# P_04__CPU_POWER.net
KiCad netlist of a schematic drawn in Altium Designer
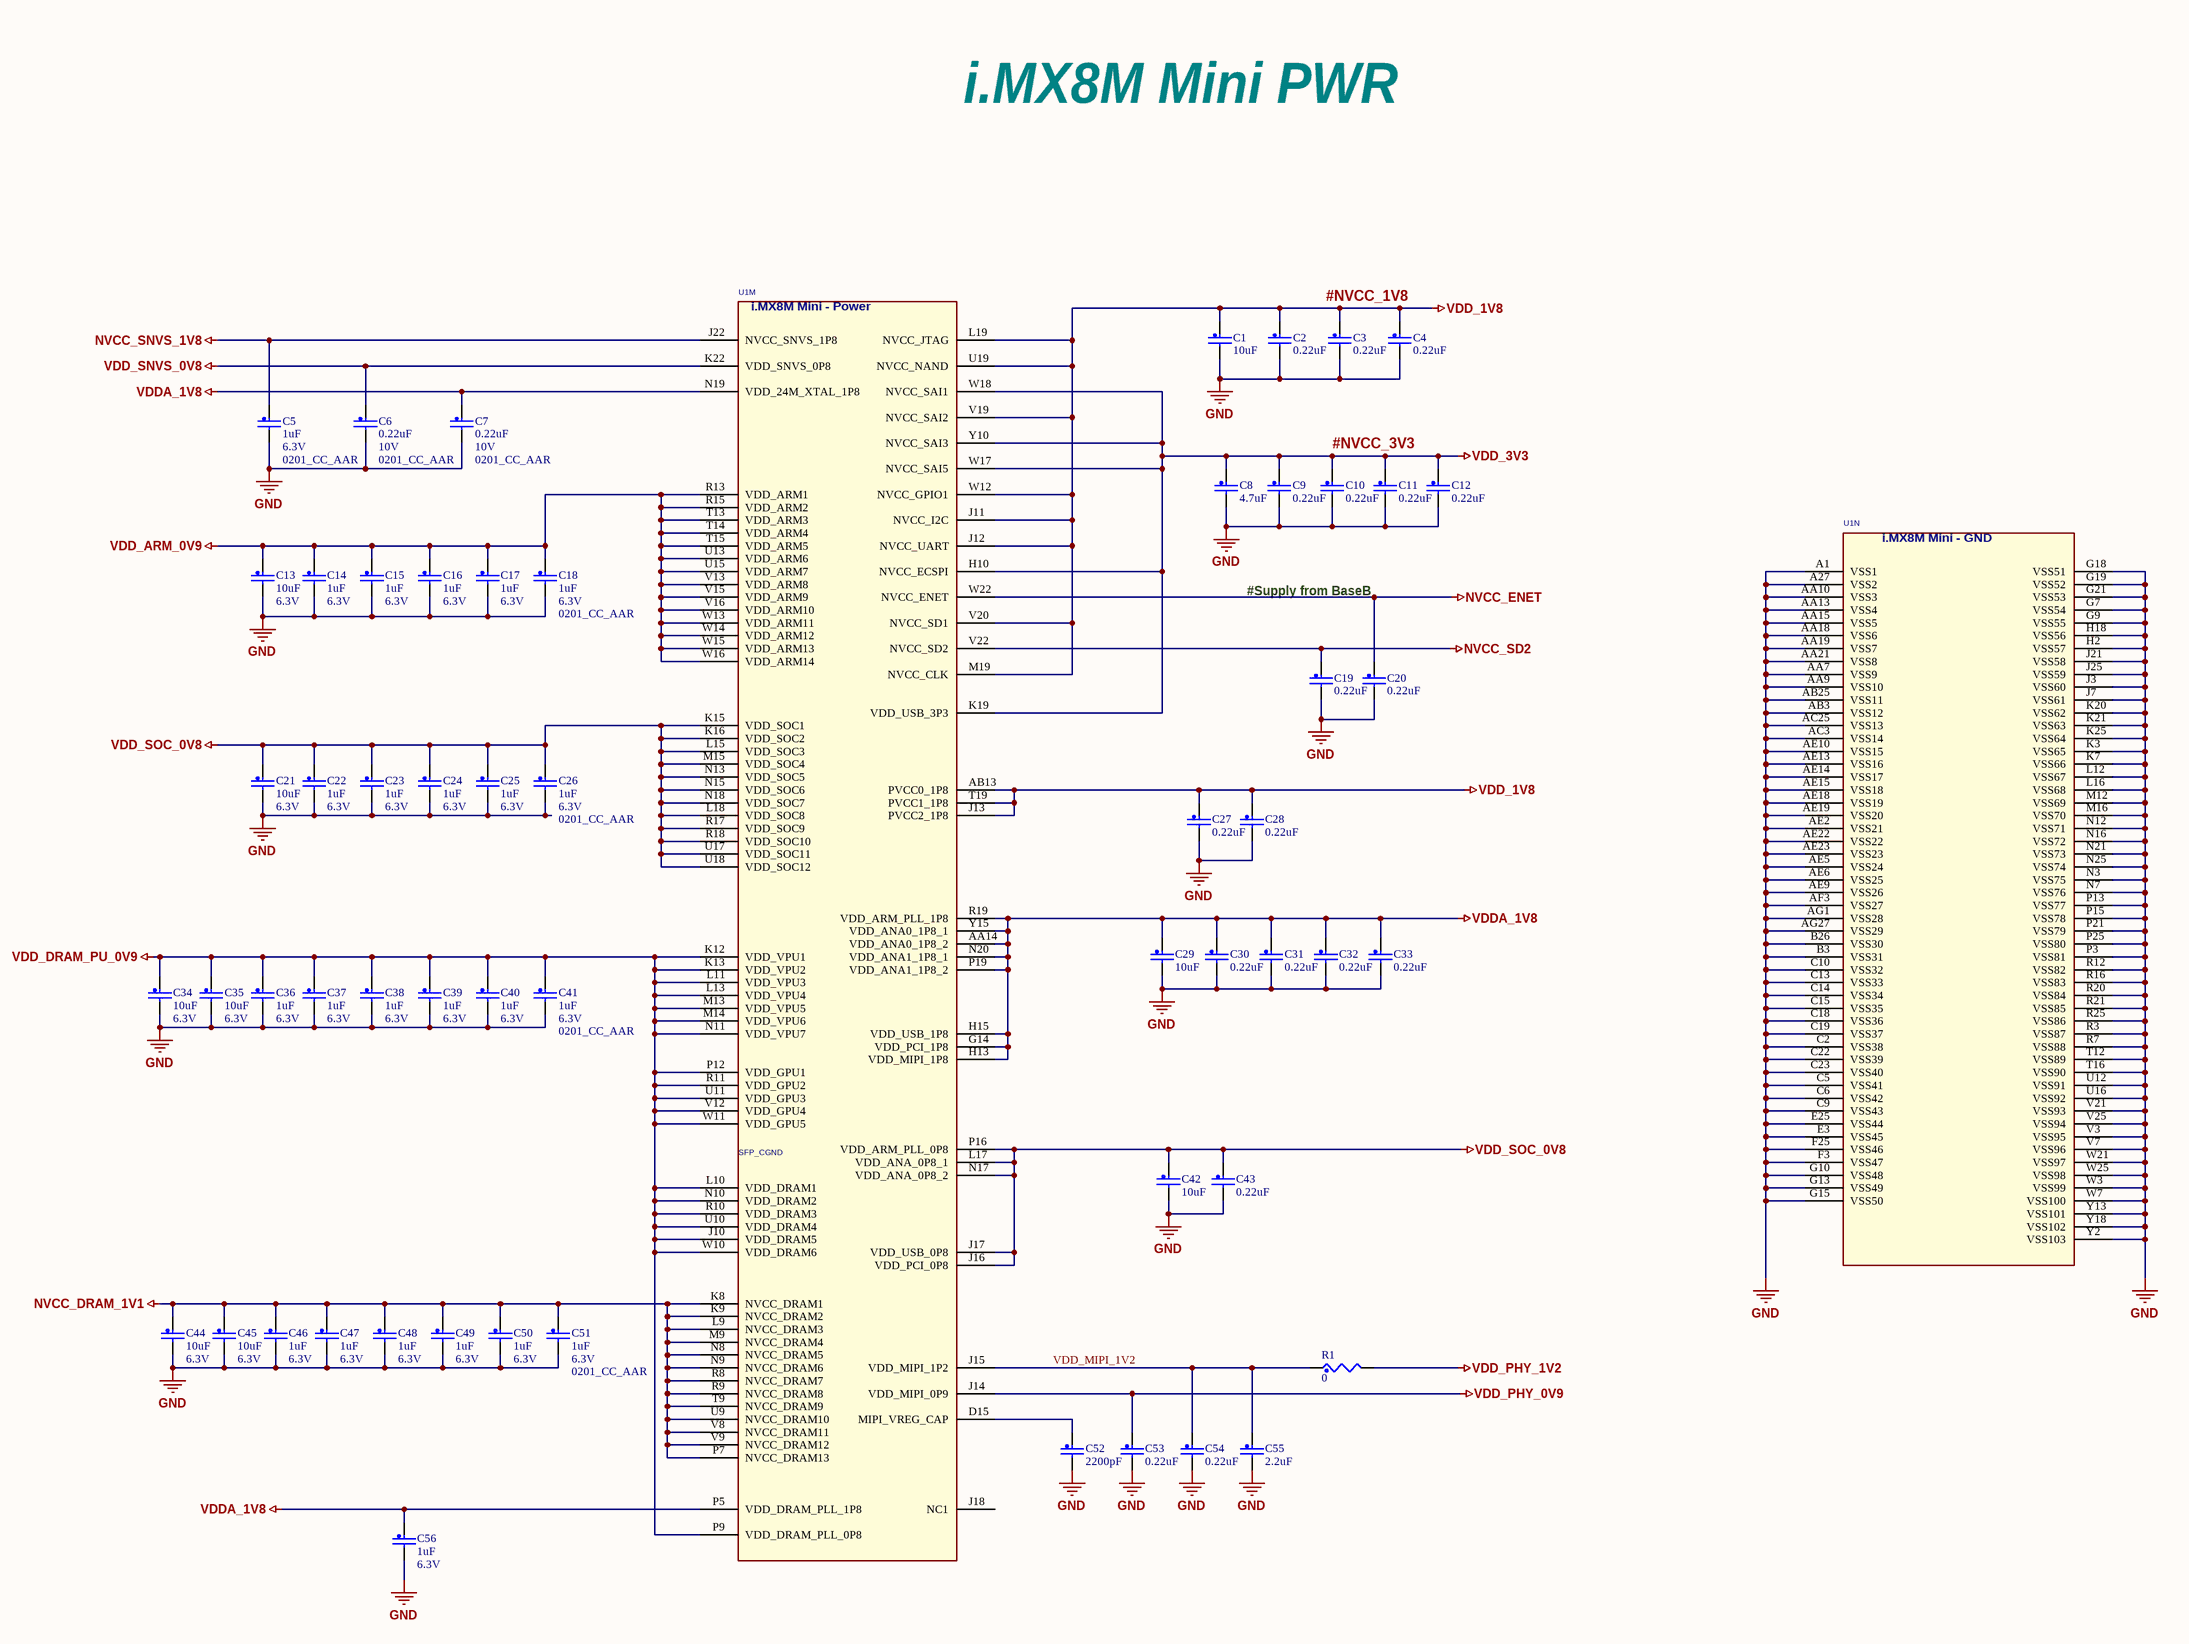
[diagram p0: P[04]_CPU_POWER.SchDoc]

(export (version "E")
  (design (tool "Eeschema 10.0.6"))
  (components
    (comp (ref "C1") (value "10uF") (footprint "0402_CC - C") (libsource (lib "AA_iMX8_M_") (part "CAP_NP")))
    (comp (ref "C2")
      (value "0.22uF")
      (footprint "0201_CC - C")
      (libsource (lib "AA_iMX8_M_") (part "CAP_NP"))
    )
    (comp (ref "C3")
      (value "0.22uF")
      (footprint "0201_CC - C")
      (libsource (lib "AA_iMX8_M_") (part "CAP_NP"))
    )
    (comp (ref "C4")
      (value "0.22uF")
      (footprint "0201_CC - C")
      (libsource (lib "AA_iMX8_M_") (part "CAP_NP"))
    )
    (comp (ref "C5")
      (value "1uF")
      (footprint "0201_CC_AAR")
      (fields (field (name "VOLTAGE") "6.3V"))
      (libsource (lib "AA_iMX8_M_") (part "CAP_NP"))
    )
    (comp (ref "C6")
      (value "0.22uF")
      (footprint "0201_CC_AAR")
      (fields (field (name "VOLTAGE") "10V"))
      (libsource (lib "AA_iMX8_M_") (part "CAP_NP"))
    )
    (comp (ref "C7")
      (value "0.22uF")
      (footprint "0201_CC_AAR")
      (fields (field (name "VOLTAGE") "10V"))
      (libsource (lib "AA_iMX8_M_") (part "CAP_NP"))
    )
    (comp (ref "C8") (value "4.7uF") (footprint "0402_CC - C") (libsource (lib "AA_iMX8_M_") (part "CAP_NP")))
    (comp (ref "C9")
      (value "0.22uF")
      (footprint "0201_CC - C")
      (libsource (lib "AA_iMX8_M_") (part "CAP_NP"))
    )
    (comp (ref "C10")
      (value "0.22uF")
      (footprint "0201_CC - C")
      (libsource (lib "AA_iMX8_M_") (part "CAP_NP"))
    )
    (comp (ref "C11")
      (value "0.22uF")
      (footprint "0201_CC - C")
      (libsource (lib "AA_iMX8_M_") (part "CAP_NP"))
    )
    (comp (ref "C12")
      (value "0.22uF")
      (footprint "0201_CC - C")
      (libsource (lib "AA_iMX8_M_") (part "CAP_NP"))
    )
    (comp (ref "C13")
      (value "10uF")
      (footprint "0402_CC - C")
      (fields (field (name "VOLTAGE") "6.3V"))
      (libsource (lib "AA_iMX8_M_") (part "CAP_NP"))
    )
    (comp (ref "C14")
      (value "1uF")
      (footprint "0201_CC - C")
      (fields (field (name "VOLTAGE") "6.3V"))
      (libsource (lib "AA_iMX8_M_") (part "CAP_NP"))
    )
    (comp (ref "C15")
      (value "1uF")
      (footprint "0201_CC - C")
      (fields (field (name "VOLTAGE") "6.3V"))
      (libsource (lib "AA_iMX8_M_") (part "CAP_NP"))
    )
    (comp (ref "C16")
      (value "1uF")
      (footprint "0201_CC - C")
      (fields (field (name "VOLTAGE") "6.3V"))
      (libsource (lib "AA_iMX8_M_") (part "CAP_NP"))
    )
    (comp (ref "C17")
      (value "1uF")
      (footprint "0201_CC - C")
      (fields (field (name "VOLTAGE") "6.3V"))
      (libsource (lib "AA_iMX8_M_") (part "CAP_NP"))
    )
    (comp (ref "C18")
      (value "1uF")
      (footprint "0201_CC_AAR")
      (fields (field (name "VOLTAGE") "6.3V"))
      (libsource (lib "AA_iMX8_M_") (part "CAP_NP"))
    )
    (comp (ref "C19")
      (value "0.22uF")
      (footprint "0201_CC - C")
      (libsource (lib "AA_iMX8_M_") (part "CAP_NP"))
    )
    (comp (ref "C20")
      (value "0.22uF")
      (footprint "0201_CC - C")
      (libsource (lib "AA_iMX8_M_") (part "CAP_NP"))
    )
    (comp (ref "C21")
      (value "10uF")
      (footprint "0402_CC - C")
      (fields (field (name "VOLTAGE") "6.3V"))
      (libsource (lib "AA_iMX8_M_") (part "CAP_NP"))
    )
    (comp (ref "C22")
      (value "1uF")
      (footprint "0201_CC - C")
      (fields (field (name "VOLTAGE") "6.3V"))
      (libsource (lib "AA_iMX8_M_") (part "CAP_NP"))
    )
    (comp (ref "C23")
      (value "1uF")
      (footprint "0201_CC - C")
      (fields (field (name "VOLTAGE") "6.3V"))
      (libsource (lib "AA_iMX8_M_") (part "CAP_NP"))
    )
    (comp (ref "C24")
      (value "1uF")
      (footprint "0201_CC - C")
      (fields (field (name "VOLTAGE") "6.3V"))
      (libsource (lib "AA_iMX8_M_") (part "CAP_NP"))
    )
    (comp (ref "C25")
      (value "1uF")
      (footprint "0201_CC - C")
      (fields (field (name "VOLTAGE") "6.3V"))
      (libsource (lib "AA_iMX8_M_") (part "CAP_NP"))
    )
    (comp (ref "C26")
      (value "1uF")
      (footprint "0201_CC_AAR")
      (fields (field (name "VOLTAGE") "6.3V"))
      (libsource (lib "AA_iMX8_M_") (part "CAP_NP"))
    )
    (comp (ref "C27")
      (value "0.22uF")
      (footprint "0201_CC - C")
      (libsource (lib "AA_iMX8_M_") (part "CAP_NP"))
    )
    (comp (ref "C28")
      (value "0.22uF")
      (footprint "0201_CC - C")
      (libsource (lib "AA_iMX8_M_") (part "CAP_NP"))
    )
    (comp (ref "C29") (value "10uF") (footprint "0402_CC - C") (libsource (lib "AA_iMX8_M_") (part "CAP_NP")))
    (comp (ref "C30")
      (value "0.22uF")
      (footprint "0201_CC - C")
      (libsource (lib "AA_iMX8_M_") (part "CAP_NP"))
    )
    (comp (ref "C31")
      (value "0.22uF")
      (footprint "0201_CC - C")
      (libsource (lib "AA_iMX8_M_") (part "CAP_NP"))
    )
    (comp (ref "C32")
      (value "0.22uF")
      (footprint "0201_CC - C")
      (libsource (lib "AA_iMX8_M_") (part "CAP_NP"))
    )
    (comp (ref "C33")
      (value "0.22uF")
      (footprint "0201_CC - C")
      (libsource (lib "AA_iMX8_M_") (part "CAP_NP"))
    )
    (comp (ref "C34")
      (value "10uF")
      (footprint "0402_CC - C")
      (fields (field (name "VOLTAGE") "6.3V"))
      (libsource (lib "AA_iMX8_M_") (part "CAP_NP"))
    )
    (comp (ref "C35")
      (value "10uF")
      (footprint "0402_CC - C")
      (fields (field (name "VOLTAGE") "6.3V"))
      (libsource (lib "AA_iMX8_M_") (part "CAP_NP"))
    )
    (comp (ref "C36")
      (value "1uF")
      (footprint "0201_CC - C")
      (fields (field (name "VOLTAGE") "6.3V"))
      (libsource (lib "AA_iMX8_M_") (part "CAP_NP"))
    )
    (comp (ref "C37")
      (value "1uF")
      (footprint "0201_CC - C")
      (fields (field (name "VOLTAGE") "6.3V"))
      (libsource (lib "AA_iMX8_M_") (part "CAP_NP"))
    )
    (comp (ref "C38")
      (value "1uF")
      (footprint "0201_CC - C")
      (fields (field (name "VOLTAGE") "6.3V"))
      (libsource (lib "AA_iMX8_M_") (part "CAP_NP"))
    )
    (comp (ref "C39")
      (value "1uF")
      (footprint "0201_CC - C")
      (fields (field (name "VOLTAGE") "6.3V"))
      (libsource (lib "AA_iMX8_M_") (part "CAP_NP"))
    )
    (comp (ref "C40")
      (value "1uF")
      (footprint "0201_CC - C")
      (fields (field (name "VOLTAGE") "6.3V"))
      (libsource (lib "AA_iMX8_M_") (part "CAP_NP"))
    )
    (comp (ref "C41")
      (value "1uF")
      (footprint "0201_CC_AAR")
      (fields (field (name "VOLTAGE") "6.3V"))
      (libsource (lib "AA_iMX8_M_") (part "CAP_NP"))
    )
    (comp (ref "C42") (value "10uF") (footprint "0402_CC - C") (libsource (lib "AA_iMX8_M_") (part "CAP_NP")))
    (comp (ref "C43")
      (value "0.22uF")
      (footprint "0201_CC - C")
      (libsource (lib "AA_iMX8_M_") (part "CAP_NP"))
    )
    (comp (ref "C44")
      (value "10uF")
      (footprint "0402_CC - C")
      (fields (field (name "VOLTAGE") "6.3V"))
      (libsource (lib "AA_iMX8_M_") (part "CAP_NP"))
    )
    (comp (ref "C45")
      (value "10uF")
      (footprint "0402_CC - C")
      (fields (field (name "VOLTAGE") "6.3V"))
      (libsource (lib "AA_iMX8_M_") (part "CAP_NP"))
    )
    (comp (ref "C46")
      (value "1uF")
      (footprint "0201_CC - C")
      (fields (field (name "VOLTAGE") "6.3V"))
      (libsource (lib "AA_iMX8_M_") (part "CAP_NP"))
    )
    (comp (ref "C47")
      (value "1uF")
      (footprint "0201_CC - C")
      (fields (field (name "VOLTAGE") "6.3V"))
      (libsource (lib "AA_iMX8_M_") (part "CAP_NP"))
    )
    (comp (ref "C48")
      (value "1uF")
      (footprint "0201_CC - C")
      (fields (field (name "VOLTAGE") "6.3V"))
      (libsource (lib "AA_iMX8_M_") (part "CAP_NP"))
    )
    (comp (ref "C49")
      (value "1uF")
      (footprint "0201_CC - C")
      (fields (field (name "VOLTAGE") "6.3V"))
      (libsource (lib "AA_iMX8_M_") (part "CAP_NP"))
    )
    (comp (ref "C50")
      (value "1uF")
      (footprint "0201_CC - C")
      (fields (field (name "VOLTAGE") "6.3V"))
      (libsource (lib "AA_iMX8_M_") (part "CAP_NP"))
    )
    (comp (ref "C51")
      (value "1uF")
      (footprint "0201_CC_AAR")
      (fields (field (name "VOLTAGE") "6.3V"))
      (libsource (lib "AA_iMX8_M_") (part "CAP_NP"))
    )
    (comp (ref "C52")
      (value "2200pF")
      (footprint "0201_CC - C")
      (libsource (lib "AA_iMX8_M_") (part "CAP_NP"))
    )
    (comp (ref "C53")
      (value "0.22uF")
      (footprint "0201_CC - C")
      (libsource (lib "AA_iMX8_M_") (part "CAP_NP"))
    )
    (comp (ref "C54")
      (value "0.22uF")
      (footprint "0201_CC - C")
      (libsource (lib "AA_iMX8_M_") (part "CAP_NP"))
    )
    (comp (ref "C55")
      (value "2.2uF")
      (footprint "0402_CC - C")
      (libsource (lib "AA_iMX8_M_") (part "CAP_NP"))
    )
    (comp (ref "C56")
      (value "1uF")
      (footprint "0201_CC - C")
      (fields (field (name "VOLTAGE") "6.3V"))
      (libsource (lib "AA_iMX8_M_") (part "CAP_NP"))
    )
    (comp (ref "R1") (value "0") (footprint "0402_CC") (libsource (lib "AA_iMX8_M_") (part "RES")))
    (comp (ref "U1")
      (value "SFP_CGND")
      (footprint "BGA486_0P5_14X14")
      (description "IC CPU QUAD CORTEX A53+M4 1.8GHZ BGA486 / By Arman Arvand")
      (libsource (lib "AA_iMX8_M_") (part "MIMX8MM_BGA486P"))
    )
  )
  (nets
    (net (code "1") (name "/VDD_MIPI_1V2") (class "Default")
      (node (ref "C54") (pin "1") (pinfunction "1_1") (pintype "passive"))
      (node (ref "C55") (pin "1") (pinfunction "1_1") (pintype "passive"))
      (node (ref "R1") (pin "1") (pinfunction "1_1") (pintype "passive"))
      (node (ref "U1") (pin "J15") (pinfunction "VDD_MIPI_1P2_J15") (pintype "power_in"))
    )
    (net (code "2") (name "GND") (class "Default")
      (node (ref "C1") (pin "2") (pinfunction "2_2") (pintype "passive"))
      (node (ref "C10") (pin "2") (pinfunction "2_2") (pintype "passive"))
      (node (ref "C11") (pin "2") (pinfunction "2_2") (pintype "passive"))
      (node (ref "C12") (pin "2") (pinfunction "2_2") (pintype "passive"))
      (node (ref "C13") (pin "2") (pinfunction "2_2") (pintype "passive"))
      (node (ref "C14") (pin "2") (pinfunction "2_2") (pintype "passive"))
      (node (ref "C15") (pin "2") (pinfunction "2_2") (pintype "passive"))
      (node (ref "C16") (pin "2") (pinfunction "2_2") (pintype "passive"))
      (node (ref "C17") (pin "2") (pinfunction "2_2") (pintype "passive"))
      (node (ref "C18") (pin "2") (pinfunction "2_2") (pintype "passive"))
      (node (ref "C19") (pin "2") (pinfunction "2_2") (pintype "passive"))
      (node (ref "C2") (pin "2") (pinfunction "2_2") (pintype "passive"))
      (node (ref "C20") (pin "2") (pinfunction "2_2") (pintype "passive"))
      (node (ref "C21") (pin "2") (pinfunction "2_2") (pintype "passive"))
      (node (ref "C22") (pin "2") (pinfunction "2_2") (pintype "passive"))
      (node (ref "C23") (pin "2") (pinfunction "2_2") (pintype "passive"))
      (node (ref "C24") (pin "2") (pinfunction "2_2") (pintype "passive"))
      (node (ref "C25") (pin "2") (pinfunction "2_2") (pintype "passive"))
      (node (ref "C26") (pin "2") (pinfunction "2_2") (pintype "passive"))
      (node (ref "C27") (pin "2") (pinfunction "2_2") (pintype "passive"))
      (node (ref "C28") (pin "2") (pinfunction "2_2") (pintype "passive"))
      (node (ref "C29") (pin "2") (pinfunction "2_2") (pintype "passive"))
      (node (ref "C3") (pin "2") (pinfunction "2_2") (pintype "passive"))
      (node (ref "C30") (pin "2") (pinfunction "2_2") (pintype "passive"))
      (node (ref "C31") (pin "2") (pinfunction "2_2") (pintype "passive"))
      (node (ref "C32") (pin "2") (pinfunction "2_2") (pintype "passive"))
      (node (ref "C33") (pin "2") (pinfunction "2_2") (pintype "passive"))
      (node (ref "C34") (pin "2") (pinfunction "2_2") (pintype "passive"))
      (node (ref "C35") (pin "2") (pinfunction "2_2") (pintype "passive"))
      (node (ref "C36") (pin "2") (pinfunction "2_2") (pintype "passive"))
      (node (ref "C37") (pin "2") (pinfunction "2_2") (pintype "passive"))
      (node (ref "C38") (pin "2") (pinfunction "2_2") (pintype "passive"))
      (node (ref "C39") (pin "2") (pinfunction "2_2") (pintype "passive"))
      (node (ref "C4") (pin "2") (pinfunction "2_2") (pintype "passive"))
      (node (ref "C40") (pin "2") (pinfunction "2_2") (pintype "passive"))
      (node (ref "C41") (pin "2") (pinfunction "2_2") (pintype "passive"))
      (node (ref "C42") (pin "2") (pinfunction "2_2") (pintype "passive"))
      (node (ref "C43") (pin "2") (pinfunction "2_2") (pintype "passive"))
      (node (ref "C44") (pin "2") (pinfunction "2_2") (pintype "passive"))
      (node (ref "C45") (pin "2") (pinfunction "2_2") (pintype "passive"))
      (node (ref "C46") (pin "2") (pinfunction "2_2") (pintype "passive"))
      (node (ref "C47") (pin "2") (pinfunction "2_2") (pintype "passive"))
      (node (ref "C48") (pin "2") (pinfunction "2_2") (pintype "passive"))
      (node (ref "C49") (pin "2") (pinfunction "2_2") (pintype "passive"))
      (node (ref "C5") (pin "2") (pinfunction "2_2") (pintype "passive"))
      (node (ref "C50") (pin "2") (pinfunction "2_2") (pintype "passive"))
      (node (ref "C51") (pin "2") (pinfunction "2_2") (pintype "passive"))
      (node (ref "C52") (pin "2") (pinfunction "2_2") (pintype "passive"))
      (node (ref "C53") (pin "2") (pinfunction "2_2") (pintype "passive"))
      (node (ref "C54") (pin "2") (pinfunction "2_2") (pintype "passive"))
      (node (ref "C55") (pin "2") (pinfunction "2_2") (pintype "passive"))
      (node (ref "C56") (pin "2") (pinfunction "2_2") (pintype "passive"))
      (node (ref "C6") (pin "2") (pinfunction "2_2") (pintype "passive"))
      (node (ref "C7") (pin "2") (pinfunction "2_2") (pintype "passive"))
      (node (ref "C8") (pin "2") (pinfunction "2_2") (pintype "passive"))
      (node (ref "C9") (pin "2") (pinfunction "2_2") (pintype "passive"))
      (node (ref "U1") (pin "A1") (pinfunction "VSS1_A1") (pintype "power_in"))
      (node (ref "U1") (pin "A27") (pinfunction "VSS2_A27") (pintype "power_in"))
      (node (ref "U1") (pin "AA10") (pinfunction "VSS3_AA10") (pintype "power_in"))
      (node (ref "U1") (pin "AA13") (pinfunction "VSS4_AA13") (pintype "power_in"))
      (node (ref "U1") (pin "AA15") (pinfunction "VSS5_AA15") (pintype "power_in"))
      (node (ref "U1") (pin "AA18") (pinfunction "VSS6_AA18") (pintype "power_in"))
      (node (ref "U1") (pin "AA19") (pinfunction "VSS7_AA19") (pintype "power_in"))
      (node (ref "U1") (pin "AA21") (pinfunction "VSS8_AA21") (pintype "power_in"))
      (node (ref "U1") (pin "AA7") (pinfunction "VSS9_AA7") (pintype "power_in"))
      (node (ref "U1") (pin "AA9") (pinfunction "VSS10_AA9") (pintype "power_in"))
      (node (ref "U1") (pin "AB25") (pinfunction "VSS11_AB25") (pintype "power_in"))
      (node (ref "U1") (pin "AB3") (pinfunction "VSS12_AB3") (pintype "power_in"))
      (node (ref "U1") (pin "AC25") (pinfunction "VSS13_AC25") (pintype "power_in"))
      (node (ref "U1") (pin "AC3") (pinfunction "VSS14_AC3") (pintype "power_in"))
      (node (ref "U1") (pin "AE10") (pinfunction "VSS15_AE10") (pintype "power_in"))
      (node (ref "U1") (pin "AE13") (pinfunction "VSS16_AE13") (pintype "power_in"))
      (node (ref "U1") (pin "AE14") (pinfunction "VSS17_AE14") (pintype "power_in"))
      (node (ref "U1") (pin "AE15") (pinfunction "VSS18_AE15") (pintype "power_in"))
      (node (ref "U1") (pin "AE18") (pinfunction "VSS19_AE18") (pintype "power_in"))
      (node (ref "U1") (pin "AE19") (pinfunction "VSS20_AE19") (pintype "power_in"))
      (node (ref "U1") (pin "AE2") (pinfunction "VSS21_AE2") (pintype "power_in"))
      (node (ref "U1") (pin "AE22") (pinfunction "VSS22_AE22") (pintype "power_in"))
      (node (ref "U1") (pin "AE23") (pinfunction "VSS23_AE23") (pintype "power_in"))
      (node (ref "U1") (pin "AE5") (pinfunction "VSS24_AE5") (pintype "power_in"))
      (node (ref "U1") (pin "AE6") (pinfunction "VSS25_AE6") (pintype "power_in"))
      (node (ref "U1") (pin "AE9") (pinfunction "VSS26_AE9") (pintype "power_in"))
      (node (ref "U1") (pin "AF3") (pinfunction "VSS27_AF3") (pintype "power_in"))
      (node (ref "U1") (pin "AG1") (pinfunction "VSS28_AG1") (pintype "power_in"))
      (node (ref "U1") (pin "AG27") (pinfunction "VSS29_AG27") (pintype "power_in"))
      (node (ref "U1") (pin "B26") (pinfunction "VSS30_B26") (pintype "power_in"))
      (node (ref "U1") (pin "B3") (pinfunction "VSS31_B3") (pintype "power_in"))
      (node (ref "U1") (pin "C10") (pinfunction "VSS32_C10") (pintype "power_in"))
      (node (ref "U1") (pin "C13") (pinfunction "VSS33_C13") (pintype "power_in"))
      (node (ref "U1") (pin "C14") (pinfunction "VSS34_C14") (pintype "power_in"))
      (node (ref "U1") (pin "C15") (pinfunction "VSS35_C15") (pintype "power_in"))
      (node (ref "U1") (pin "C18") (pinfunction "VSS36_C18") (pintype "power_in"))
      (node (ref "U1") (pin "C19") (pinfunction "VSS37_C19") (pintype "power_in"))
      (node (ref "U1") (pin "C2") (pinfunction "VSS38_C2") (pintype "power_in"))
      (node (ref "U1") (pin "C22") (pinfunction "VSS39_C22") (pintype "power_in"))
      (node (ref "U1") (pin "C23") (pinfunction "VSS40_C23") (pintype "power_in"))
      (node (ref "U1") (pin "C5") (pinfunction "VSS41_C5") (pintype "power_in"))
      (node (ref "U1") (pin "C6") (pinfunction "VSS42_C6") (pintype "power_in"))
      (node (ref "U1") (pin "C9") (pinfunction "VSS43_C9") (pintype "power_in"))
      (node (ref "U1") (pin "E25") (pinfunction "VSS44_E25") (pintype "power_in"))
      (node (ref "U1") (pin "E3") (pinfunction "VSS45_E3") (pintype "power_in"))
      (node (ref "U1") (pin "F25") (pinfunction "VSS46_F25") (pintype "power_in"))
      (node (ref "U1") (pin "F3") (pinfunction "VSS47_F3") (pintype "power_in"))
      (node (ref "U1") (pin "G10") (pinfunction "VSS48_G10") (pintype "power_in"))
      (node (ref "U1") (pin "G13") (pinfunction "VSS49_G13") (pintype "power_in"))
      (node (ref "U1") (pin "G15") (pinfunction "VSS50_G15") (pintype "power_in"))
      (node (ref "U1") (pin "G18") (pinfunction "VSS51_G18") (pintype "power_in"))
      (node (ref "U1") (pin "G19") (pinfunction "VSS52_G19") (pintype "power_in"))
      (node (ref "U1") (pin "G21") (pinfunction "VSS53_G21") (pintype "power_in"))
      (node (ref "U1") (pin "G7") (pinfunction "VSS54_G7") (pintype "power_in"))
      (node (ref "U1") (pin "G9") (pinfunction "VSS55_G9") (pintype "power_in"))
      (node (ref "U1") (pin "H18") (pinfunction "VSS56_H18") (pintype "power_in"))
      (node (ref "U1") (pin "H2") (pinfunction "VSS57_H2") (pintype "power_in"))
      (node (ref "U1") (pin "J21") (pinfunction "VSS58_J21") (pintype "power_in"))
      (node (ref "U1") (pin "J25") (pinfunction "VSS59_J25") (pintype "power_in"))
      (node (ref "U1") (pin "J3") (pinfunction "VSS60_J3") (pintype "power_in"))
      (node (ref "U1") (pin "J7") (pinfunction "VSS61_J7") (pintype "power_in"))
      (node (ref "U1") (pin "K20") (pinfunction "VSS62_K20") (pintype "power_in"))
      (node (ref "U1") (pin "K21") (pinfunction "VSS63_K21") (pintype "power_in"))
      (node (ref "U1") (pin "K25") (pinfunction "VSS64_K25") (pintype "power_in"))
      (node (ref "U1") (pin "K3") (pinfunction "VSS65_K3") (pintype "power_in"))
      (node (ref "U1") (pin "K7") (pinfunction "VSS66_K7") (pintype "power_in"))
      (node (ref "U1") (pin "L12") (pinfunction "VSS67_L12") (pintype "power_in"))
      (node (ref "U1") (pin "L16") (pinfunction "VSS68_L16") (pintype "power_in"))
      (node (ref "U1") (pin "M12") (pinfunction "VSS69_M12") (pintype "power_in"))
      (node (ref "U1") (pin "M16") (pinfunction "VSS70_M16") (pintype "power_in"))
      (node (ref "U1") (pin "N12") (pinfunction "VSS71_N12") (pintype "power_in"))
      (node (ref "U1") (pin "N16") (pinfunction "VSS72_N16") (pintype "power_in"))
      (node (ref "U1") (pin "N21") (pinfunction "VSS73_N21") (pintype "power_in"))
      (node (ref "U1") (pin "N25") (pinfunction "VSS74_N25") (pintype "power_in"))
      (node (ref "U1") (pin "N3") (pinfunction "VSS75_N3") (pintype "power_in"))
      (node (ref "U1") (pin "N7") (pinfunction "VSS76_N7") (pintype "power_in"))
      (node (ref "U1") (pin "P13") (pinfunction "VSS77_P13") (pintype "power_in"))
      (node (ref "U1") (pin "P15") (pinfunction "VSS78_P15") (pintype "power_in"))
      (node (ref "U1") (pin "P21") (pinfunction "VSS79_P21") (pintype "power_in"))
      (node (ref "U1") (pin "P25") (pinfunction "VSS80_P25") (pintype "power_in"))
      (node (ref "U1") (pin "P3") (pinfunction "VSS81_P3") (pintype "power_in"))
      (node (ref "U1") (pin "R12") (pinfunction "VSS82_R12") (pintype "power_in"))
      (node (ref "U1") (pin "R16") (pinfunction "VSS83_R16") (pintype "power_in"))
      (node (ref "U1") (pin "R20") (pinfunction "VSS84_R20") (pintype "power_in"))
      (node (ref "U1") (pin "R21") (pinfunction "VSS85_R21") (pintype "power_in"))
      (node (ref "U1") (pin "R25") (pinfunction "VSS86_R25") (pintype "power_in"))
      (node (ref "U1") (pin "R3") (pinfunction "VSS87_R3") (pintype "power_in"))
      (node (ref "U1") (pin "R7") (pinfunction "VSS88_R7") (pintype "power_in"))
      (node (ref "U1") (pin "T12") (pinfunction "VSS89_T12") (pintype "power_in"))
      (node (ref "U1") (pin "T16") (pinfunction "VSS90_T16") (pintype "power_in"))
      (node (ref "U1") (pin "U12") (pinfunction "VSS91_U12") (pintype "power_in"))
      (node (ref "U1") (pin "U16") (pinfunction "VSS92_U16") (pintype "power_in"))
      (node (ref "U1") (pin "V21") (pinfunction "VSS93_V21") (pintype "power_in"))
      (node (ref "U1") (pin "V25") (pinfunction "VSS94_V25") (pintype "power_in"))
      (node (ref "U1") (pin "V3") (pinfunction "VSS95_V3") (pintype "power_in"))
      (node (ref "U1") (pin "V7") (pinfunction "VSS96_V7") (pintype "power_in"))
      (node (ref "U1") (pin "W21") (pinfunction "VSS97_W21") (pintype "power_in"))
      (node (ref "U1") (pin "W25") (pinfunction "VSS98_W25") (pintype "power_in"))
      (node (ref "U1") (pin "W3") (pinfunction "VSS99_W3") (pintype "power_in"))
      (node (ref "U1") (pin "W7") (pinfunction "VSS100_W7") (pintype "power_in"))
      (node (ref "U1") (pin "Y13") (pinfunction "VSS101_Y13") (pintype "power_in"))
      (node (ref "U1") (pin "Y18") (pinfunction "VSS102_Y18") (pintype "power_in"))
      (node (ref "U1") (pin "Y2") (pinfunction "VSS103_Y2") (pintype "power_in"))
    )
    (net (code "3") (name "NVCC_DRAM_1V1") (class "Default")
      (node (ref "C44") (pin "1") (pinfunction "1_1") (pintype "passive"))
      (node (ref "C45") (pin "1") (pinfunction "1_1") (pintype "passive"))
      (node (ref "C46") (pin "1") (pinfunction "1_1") (pintype "passive"))
      (node (ref "C47") (pin "1") (pinfunction "1_1") (pintype "passive"))
      (node (ref "C48") (pin "1") (pinfunction "1_1") (pintype "passive"))
      (node (ref "C49") (pin "1") (pinfunction "1_1") (pintype "passive"))
      (node (ref "C50") (pin "1") (pinfunction "1_1") (pintype "passive"))
      (node (ref "C51") (pin "1") (pinfunction "1_1") (pintype "passive"))
      (node (ref "U1") (pin "K8") (pinfunction "NVCC_DRAM1_K8") (pintype "power_in"))
      (node (ref "U1") (pin "K9") (pinfunction "NVCC_DRAM2_K9") (pintype "power_in"))
      (node (ref "U1") (pin "L9") (pinfunction "NVCC_DRAM3_L9") (pintype "power_in"))
      (node (ref "U1") (pin "M9") (pinfunction "NVCC_DRAM4_M9") (pintype "power_in"))
      (node (ref "U1") (pin "N8") (pinfunction "NVCC_DRAM5_N8") (pintype "power_in"))
      (node (ref "U1") (pin "N9") (pinfunction "NVCC_DRAM6_N9") (pintype "power_in"))
      (node (ref "U1") (pin "P7") (pinfunction "NVCC_DRAM13_P7") (pintype "passive"))
      (node (ref "U1") (pin "R8") (pinfunction "NVCC_DRAM7_R8") (pintype "power_in"))
      (node (ref "U1") (pin "R9") (pinfunction "NVCC_DRAM8_R9") (pintype "power_in"))
      (node (ref "U1") (pin "T9") (pinfunction "NVCC_DRAM9_T9") (pintype "power_in"))
      (node (ref "U1") (pin "U9") (pinfunction "NVCC_DRAM10_U9") (pintype "power_in"))
      (node (ref "U1") (pin "V8") (pinfunction "NVCC_DRAM11_V8") (pintype "power_in"))
      (node (ref "U1") (pin "V9") (pinfunction "NVCC_DRAM12_V9") (pintype "power_in"))
    )
    (net (code "4") (name "NVCC_ENET") (class "Default")
      (node (ref "C20") (pin "1") (pinfunction "1_1") (pintype "passive"))
      (node (ref "U1") (pin "W22") (pinfunction "NVCC_ENET_W22") (pintype "power_in"))
    )
    (net (code "5") (name "NVCC_SD2") (class "Default")
      (node (ref "C19") (pin "1") (pinfunction "1_1") (pintype "passive"))
      (node (ref "U1") (pin "V22") (pinfunction "NVCC_SD2_V22") (pintype "power_in"))
    )
    (net (code "6") (name "NVCC_SNVS_1V8") (class "Default")
      (node (ref "C5") (pin "1") (pinfunction "1_1") (pintype "passive"))
      (node (ref "U1") (pin "J22") (pinfunction "NVCC_SNVS_1P8_J22") (pintype "power_in"))
    )
    (net (code "7") (name "Net-(U1M-MIPI_VREG_CAP)") (class "Default")
      (node (ref "C52") (pin "1") (pinfunction "1_1") (pintype "passive"))
      (node (ref "U1") (pin "D15") (pinfunction "MIPI_VREG_CAP_D15") (pintype "passive"))
    )
    (net (code "8") (name "VDDA_1V8") (class "Default")
      (node (ref "C29") (pin "1") (pinfunction "1_1") (pintype "passive"))
      (node (ref "C30") (pin "1") (pinfunction "1_1") (pintype "passive"))
      (node (ref "C31") (pin "1") (pinfunction "1_1") (pintype "passive"))
      (node (ref "C32") (pin "1") (pinfunction "1_1") (pintype "passive"))
      (node (ref "C33") (pin "1") (pinfunction "1_1") (pintype "passive"))
      (node (ref "C56") (pin "1") (pinfunction "1_1") (pintype "passive"))
      (node (ref "C7") (pin "1") (pinfunction "1_1") (pintype "passive"))
      (node (ref "U1") (pin "AA14") (pinfunction "VDD_ANA0_1P8_2_AA14") (pintype "power_in"))
      (node (ref "U1") (pin "G14") (pinfunction "VDD_PCI_1P8_G14") (pintype "power_in"))
      (node (ref "U1") (pin "H13") (pinfunction "VDD_MIPI_1P8_H13") (pintype "power_in"))
      (node (ref "U1") (pin "H15") (pinfunction "VDD_USB_1P8_H15") (pintype "power_in"))
      (node (ref "U1") (pin "N19") (pinfunction "VDD_24M_XTAL_1P8_N19") (pintype "power_in"))
      (node (ref "U1") (pin "N20") (pinfunction "VDD_ANA1_1P8_1_N20") (pintype "power_in"))
      (node (ref "U1") (pin "P19") (pinfunction "VDD_ANA1_1P8_2_P19") (pintype "power_in"))
      (node (ref "U1") (pin "P5") (pinfunction "VDD_DRAM_PLL_1P8_P5") (pintype "power_in"))
      (node (ref "U1") (pin "R19") (pinfunction "VDD_ARM_PLL_1P8_R19") (pintype "power_in"))
      (node (ref "U1") (pin "Y15") (pinfunction "VDD_ANA0_1P8_1_Y15") (pintype "power_in"))
    )
    (net (code "9") (name "VDD_1V8") (class "Default")
      (node (ref "C1") (pin "1") (pinfunction "1_1") (pintype "passive"))
      (node (ref "C2") (pin "1") (pinfunction "1_1") (pintype "passive"))
      (node (ref "C27") (pin "1") (pinfunction "1_1") (pintype "passive"))
      (node (ref "C28") (pin "1") (pinfunction "1_1") (pintype "passive"))
      (node (ref "C3") (pin "1") (pinfunction "1_1") (pintype "passive"))
      (node (ref "C4") (pin "1") (pinfunction "1_1") (pintype "passive"))
      (node (ref "U1") (pin "AB13") (pinfunction "PVCC0_1P8_AB13") (pintype "power_in"))
      (node (ref "U1") (pin "J11") (pinfunction "NVCC_I2C_J11") (pintype "power_in"))
      (node (ref "U1") (pin "J12") (pinfunction "NVCC_UART_J12") (pintype "power_in"))
      (node (ref "U1") (pin "J13") (pinfunction "PVCC2_1P8_J13") (pintype "power_in"))
      (node (ref "U1") (pin "L19") (pinfunction "NVCC_JTAG_L19") (pintype "power_in"))
      (node (ref "U1") (pin "M19") (pinfunction "NVCC_CLK_M19") (pintype "power_in"))
      (node (ref "U1") (pin "T19") (pinfunction "PVCC1_1P8_T19") (pintype "power_in"))
      (node (ref "U1") (pin "U19") (pinfunction "NVCC_NAND_U19") (pintype "power_in"))
      (node (ref "U1") (pin "V19") (pinfunction "NVCC_SAI2_V19") (pintype "power_in"))
      (node (ref "U1") (pin "V20") (pinfunction "NVCC_SD1_V20") (pintype "power_in"))
      (node (ref "U1") (pin "W12") (pinfunction "NVCC_GPIO1_W12") (pintype "power_in"))
    )
    (net (code "10") (name "VDD_3V3") (class "Default")
      (node (ref "C10") (pin "1") (pinfunction "1_1") (pintype "passive"))
      (node (ref "C11") (pin "1") (pinfunction "1_1") (pintype "passive"))
      (node (ref "C12") (pin "1") (pinfunction "1_1") (pintype "passive"))
      (node (ref "C8") (pin "1") (pinfunction "1_1") (pintype "passive"))
      (node (ref "C9") (pin "1") (pinfunction "1_1") (pintype "passive"))
      (node (ref "U1") (pin "H10") (pinfunction "NVCC_ECSPI_H10") (pintype "power_in"))
      (node (ref "U1") (pin "K19") (pinfunction "VDD_USB_3P3_K19") (pintype "power_in"))
      (node (ref "U1") (pin "W17") (pinfunction "NVCC_SAI5_W17") (pintype "power_in"))
      (node (ref "U1") (pin "W18") (pinfunction "NVCC_SAI1_W18") (pintype "power_in"))
      (node (ref "U1") (pin "Y10") (pinfunction "NVCC_SAI3_Y10") (pintype "power_in"))
    )
    (net (code "11") (name "VDD_ARM_0V9") (class "Default")
      (node (ref "C13") (pin "1") (pinfunction "1_1") (pintype "passive"))
      (node (ref "C14") (pin "1") (pinfunction "1_1") (pintype "passive"))
      (node (ref "C15") (pin "1") (pinfunction "1_1") (pintype "passive"))
      (node (ref "C16") (pin "1") (pinfunction "1_1") (pintype "passive"))
      (node (ref "C17") (pin "1") (pinfunction "1_1") (pintype "passive"))
      (node (ref "C18") (pin "1") (pinfunction "1_1") (pintype "passive"))
      (node (ref "U1") (pin "R13") (pinfunction "VDD_ARM1_R13") (pintype "power_in"))
      (node (ref "U1") (pin "R15") (pinfunction "VDD_ARM2_R15") (pintype "power_in"))
      (node (ref "U1") (pin "T13") (pinfunction "VDD_ARM3_T13") (pintype "power_in"))
      (node (ref "U1") (pin "T14") (pinfunction "VDD_ARM4_T14") (pintype "power_in"))
      (node (ref "U1") (pin "T15") (pinfunction "VDD_ARM5_T15") (pintype "power_in"))
      (node (ref "U1") (pin "U13") (pinfunction "VDD_ARM6_U13") (pintype "power_in"))
      (node (ref "U1") (pin "U15") (pinfunction "VDD_ARM7_U15") (pintype "power_in"))
      (node (ref "U1") (pin "V13") (pinfunction "VDD_ARM8_V13") (pintype "power_in"))
      (node (ref "U1") (pin "V15") (pinfunction "VDD_ARM9_V15") (pintype "power_in"))
      (node (ref "U1") (pin "V16") (pinfunction "VDD_ARM10_V16") (pintype "power_in"))
      (node (ref "U1") (pin "W13") (pinfunction "VDD_ARM11_W13") (pintype "power_in"))
      (node (ref "U1") (pin "W14") (pinfunction "VDD_ARM12_W14") (pintype "power_in"))
      (node (ref "U1") (pin "W15") (pinfunction "VDD_ARM13_W15") (pintype "power_in"))
      (node (ref "U1") (pin "W16") (pinfunction "VDD_ARM14_W16") (pintype "power_in"))
    )
    (net (code "12") (name "VDD_DRAM_PU_0V9") (class "Default")
      (node (ref "C34") (pin "1") (pinfunction "1_1") (pintype "passive"))
      (node (ref "C35") (pin "1") (pinfunction "1_1") (pintype "passive"))
      (node (ref "C36") (pin "1") (pinfunction "1_1") (pintype "passive"))
      (node (ref "C37") (pin "1") (pinfunction "1_1") (pintype "passive"))
      (node (ref "C38") (pin "1") (pinfunction "1_1") (pintype "passive"))
      (node (ref "C39") (pin "1") (pinfunction "1_1") (pintype "passive"))
      (node (ref "C40") (pin "1") (pinfunction "1_1") (pintype "passive"))
      (node (ref "C41") (pin "1") (pinfunction "1_1") (pintype "passive"))
      (node (ref "U1") (pin "J10") (pinfunction "VDD_DRAM5_J10") (pintype "power_in"))
      (node (ref "U1") (pin "K12") (pinfunction "VDD_VPU1_K12") (pintype "power_in"))
      (node (ref "U1") (pin "K13") (pinfunction "VDD_VPU2_K13") (pintype "power_in"))
      (node (ref "U1") (pin "L10") (pinfunction "VDD_DRAM1_L10") (pintype "power_in"))
      (node (ref "U1") (pin "L11") (pinfunction "VDD_VPU3_L11") (pintype "power_in"))
      (node (ref "U1") (pin "L13") (pinfunction "VDD_VPU4_L13") (pintype "power_in"))
      (node (ref "U1") (pin "M13") (pinfunction "VDD_VPU5_M13") (pintype "power_in"))
      (node (ref "U1") (pin "M14") (pinfunction "VDD_VPU6_M14") (pintype "power_in"))
      (node (ref "U1") (pin "N10") (pinfunction "VDD_DRAM2_N10") (pintype "power_in"))
      (node (ref "U1") (pin "N11") (pinfunction "VDD_VPU7_N11") (pintype "power_in"))
      (node (ref "U1") (pin "P12") (pinfunction "VDD_GPU1_P12") (pintype "power_in"))
      (node (ref "U1") (pin "P9") (pinfunction "VDD_DRAM_PLL_0P8_P9") (pintype "power_in"))
      (node (ref "U1") (pin "R10") (pinfunction "VDD_DRAM3_R10") (pintype "power_in"))
      (node (ref "U1") (pin "R11") (pinfunction "VDD_GPU2_R11") (pintype "power_in"))
      (node (ref "U1") (pin "U10") (pinfunction "VDD_DRAM4_U10") (pintype "power_in"))
      (node (ref "U1") (pin "U11") (pinfunction "VDD_GPU3_U11") (pintype "power_in"))
      (node (ref "U1") (pin "V12") (pinfunction "VDD_GPU4_V12") (pintype "power_in"))
      (node (ref "U1") (pin "W10") (pinfunction "VDD_DRAM6_W10") (pintype "power_in"))
      (node (ref "U1") (pin "W11") (pinfunction "VDD_GPU5_W11") (pintype "power_in"))
    )
    (net (code "13") (name "VDD_PHY_0V9") (class "Default")
      (node (ref "C53") (pin "1") (pinfunction "1_1") (pintype "passive"))
      (node (ref "U1") (pin "J14") (pinfunction "VDD_MIPI_0P9_J14") (pintype "power_in"))
    )
    (net (code "14") (name "VDD_PHY_1V2") (class "Default")
      (node (ref "R1") (pin "2") (pinfunction "2_2") (pintype "passive"))
    )
    (net (code "15") (name "VDD_SNVS_0V8") (class "Default")
      (node (ref "C6") (pin "1") (pinfunction "1_1") (pintype "passive"))
      (node (ref "U1") (pin "K22") (pinfunction "VDD_SNVS_0P8_K22") (pintype "power_in"))
    )
    (net (code "16") (name "VDD_SOC_0V8") (class "Default")
      (node (ref "C21") (pin "1") (pinfunction "1_1") (pintype "passive"))
      (node (ref "C22") (pin "1") (pinfunction "1_1") (pintype "passive"))
      (node (ref "C23") (pin "1") (pinfunction "1_1") (pintype "passive"))
      (node (ref "C24") (pin "1") (pinfunction "1_1") (pintype "passive"))
      (node (ref "C25") (pin "1") (pinfunction "1_1") (pintype "passive"))
      (node (ref "C26") (pin "1") (pinfunction "1_1") (pintype "passive"))
      (node (ref "C42") (pin "1") (pinfunction "1_1") (pintype "passive"))
      (node (ref "C43") (pin "1") (pinfunction "1_1") (pintype "passive"))
      (node (ref "U1") (pin "J16") (pinfunction "VDD_PCI_0P8_J16") (pintype "power_in"))
      (node (ref "U1") (pin "J17") (pinfunction "VDD_USB_0P8_J17") (pintype "power_in"))
      (node (ref "U1") (pin "K15") (pinfunction "VDD_SOC1_K15") (pintype "power_in"))
      (node (ref "U1") (pin "K16") (pinfunction "VDD_SOC2_K16") (pintype "power_in"))
      (node (ref "U1") (pin "L15") (pinfunction "VDD_SOC3_L15") (pintype "power_in"))
      (node (ref "U1") (pin "L17") (pinfunction "VDD_ANA_0P8_1_L17") (pintype "power_in"))
      (node (ref "U1") (pin "L18") (pinfunction "VDD_SOC8_L18") (pintype "power_in"))
      (node (ref "U1") (pin "M15") (pinfunction "VDD_SOC4_M15") (pintype "power_in"))
      (node (ref "U1") (pin "N13") (pinfunction "VDD_SOC5_N13") (pintype "power_in"))
      (node (ref "U1") (pin "N15") (pinfunction "VDD_SOC6_N15") (pintype "power_in"))
      (node (ref "U1") (pin "N17") (pinfunction "VDD_ANA_0P8_2_N17") (pintype "power_in"))
      (node (ref "U1") (pin "N18") (pinfunction "VDD_SOC7_N18") (pintype "power_in"))
      (node (ref "U1") (pin "P16") (pinfunction "VDD_ARM_PLL_0P8_P16") (pintype "power_in"))
      (node (ref "U1") (pin "R17") (pinfunction "VDD_SOC9_R17") (pintype "power_in"))
      (node (ref "U1") (pin "R18") (pinfunction "VDD_SOC10_R18") (pintype "power_in"))
      (node (ref "U1") (pin "U17") (pinfunction "VDD_SOC11_U17") (pintype "power_in"))
      (node (ref "U1") (pin "U18") (pinfunction "VDD_SOC12_U18") (pintype "power_in"))
    )
    (net (code "17") (name "unconnected-(U1M-NC1-PadJ18)") (class "Default")
      (node (ref "U1") (pin "J18") (pinfunction "NC1_J18") (pintype "power_in"))
    )
  )
)
